# Sensor-TSL45315.net
KiCad netlist of a schematic drawn in EAGLE
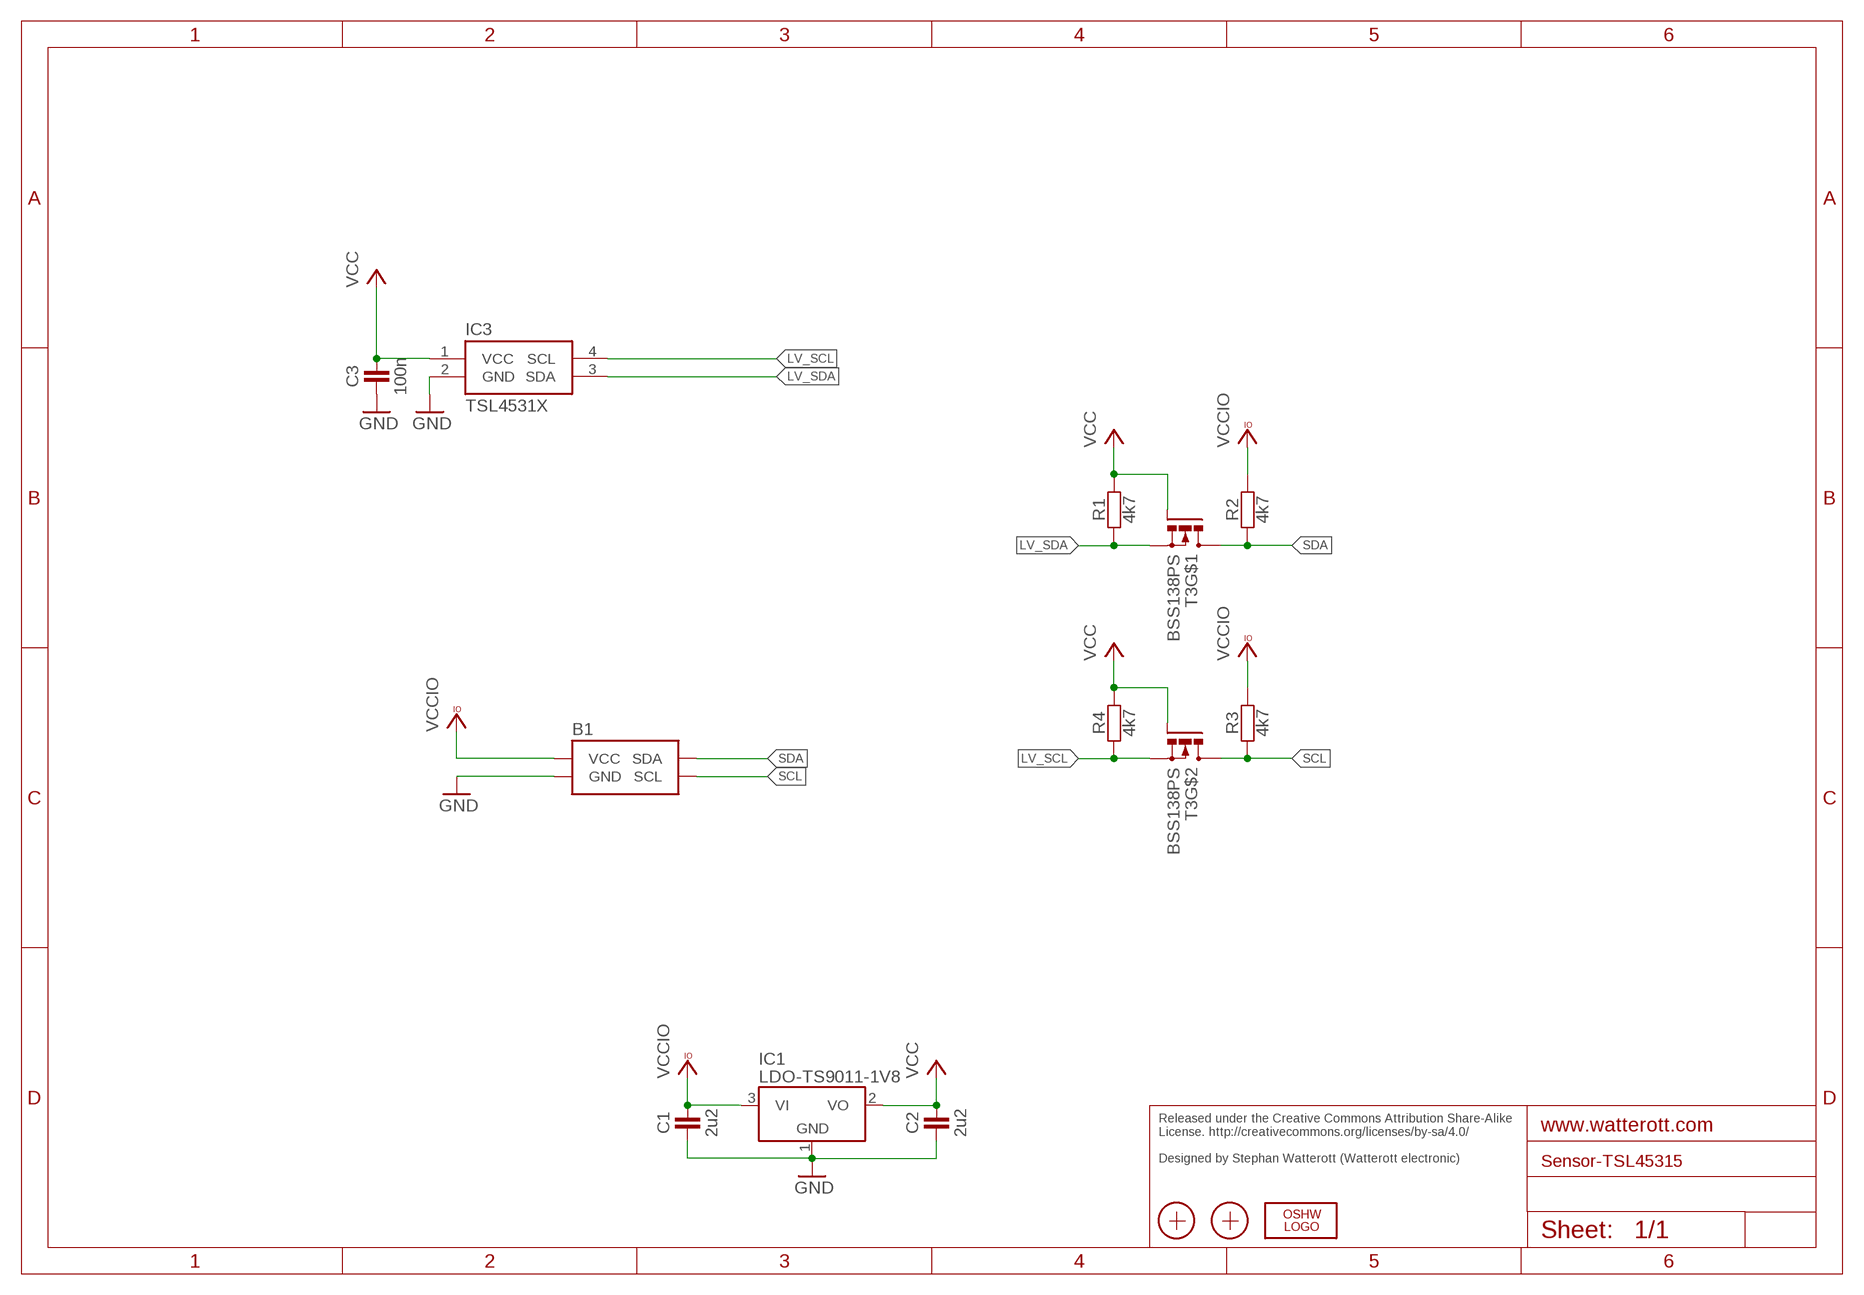
[diagram p0: schematic, sheet 1]

(export (version "E")
  (design (tool "Eeschema 10.0.6"))
  (components
    (comp (ref "B1")
      (value "SENSEBOX_I2C")
      (footprint "eagle-import:SENSEBOX_I2C")
      (libsource (lib "eagle-import") (part "SENSEBOX_I2C"))
    )
    (comp (ref "C1")
      (value "2u2")
      (footprint "eagle-import:R0402")
      (libsource (lib "eagle-import") (part "CAPACITOR-C0402"))
    )
    (comp (ref "C2")
      (value "2u2")
      (footprint "eagle-import:R0402")
      (libsource (lib "eagle-import") (part "CAPACITOR-C0402"))
    )
    (comp (ref "C3")
      (value "100n")
      (footprint "eagle-import:R0402")
      (libsource (lib "eagle-import") (part "CAPACITOR-C0402"))
    )
    (comp (ref "IC1")
      (value "LDO-TS9011-1V8")
      (footprint "eagle-import:SOT23")
      (libsource (lib "eagle-import") (part "LDO-TS9011-3V3"))
    )
    (comp (ref "IC3")
      (value "TSL4531X")
      (footprint "eagle-import:AMS_CL")
      (libsource (lib "eagle-import") (part "TSL4531X"))
    )
    (comp (ref "LOGO2")
      (value "OSHW_LOGOX0070")
      (footprint "eagle-import:OSHW_6X70")
      (libsource (lib "eagle-import") (part "OSHW_LOGOX0070"))
    )
    (comp (ref "R1")
      (value "4k7")
      (footprint "eagle-import:R0402")
      (libsource (lib "eagle-import") (part "RESISTOR-R0402"))
    )
    (comp (ref "R2")
      (value "4k7")
      (footprint "eagle-import:R0402")
      (libsource (lib "eagle-import") (part "RESISTOR-R0402"))
    )
    (comp (ref "R3")
      (value "4k7")
      (footprint "eagle-import:R0402")
      (libsource (lib "eagle-import") (part "RESISTOR-R0402"))
    )
    (comp (ref "R4")
      (value "4k7")
      (footprint "eagle-import:R0402")
      (libsource (lib "eagle-import") (part "RESISTOR-R0402"))
    )
    (comp (ref "T3")
      (value "BSS138PS")
      (footprint "eagle-import:SOT363")
      (libsource (lib "eagle-import") (part "BSS138PS"))
    )
    (comp (ref "X1")
      (value "PASSER-07")
      (footprint "eagle-import:PASSER_07MM")
      (libsource (lib "eagle-import") (part "PASSER-07"))
    )
    (comp (ref "X2")
      (value "PASSER-07")
      (footprint "eagle-import:PASSER_07MM")
      (libsource (lib "eagle-import") (part "PASSER-07"))
    )
  )
  (nets
    (net (code "1") (name "GND") (class "Default")
      (node (ref "B1") (pin "GND") (pinfunction "GND_GND") (pintype "power_in"))
      (node (ref "C1") (pin "1") (pinfunction "1_1") (pintype "passive"))
      (node (ref "C2") (pin "1") (pinfunction "1_1") (pintype "passive"))
      (node (ref "C3") (pin "1") (pinfunction "1_1") (pintype "passive"))
      (node (ref "IC1") (pin "1") (pinfunction "GND_1") (pintype "passive"))
      (node (ref "IC3") (pin "2") (pinfunction "GND_2") (pintype "power_in"))
    )
    (net (code "2") (name "LV_SCL") (class "Default")
      (node (ref "IC3") (pin "4") (pinfunction "SCL_4") (pintype "input"))
      (node (ref "R4") (pin "1") (pinfunction "1_1") (pintype "passive"))
      (node (ref "T3") (pin "4") (pinfunction "S_4") (pintype "passive"))
    )
    (net (code "3") (name "LV_SDA") (class "Default")
      (node (ref "IC3") (pin "3") (pinfunction "SDA_3") (pintype "output"))
      (node (ref "R1") (pin "1") (pinfunction "1_1") (pintype "passive"))
      (node (ref "T3") (pin "1") (pinfunction "S_1") (pintype "passive"))
    )
    (net (code "4") (name "SCL") (class "Default")
      (node (ref "B1") (pin "SCL") (pinfunction "SCL_SCL") (pintype "bidirectional"))
      (node (ref "R3") (pin "1") (pinfunction "1_1") (pintype "passive"))
      (node (ref "T3") (pin "3") (pinfunction "D_3") (pintype "passive"))
    )
    (net (code "5") (name "SDA") (class "Default")
      (node (ref "B1") (pin "SDA") (pinfunction "SDA_SDA") (pintype "bidirectional"))
      (node (ref "R2") (pin "1") (pinfunction "1_1") (pintype "passive"))
      (node (ref "T3") (pin "6") (pinfunction "D_6") (pintype "passive"))
    )
    (net (code "6") (name "VCC") (class "Default")
      (node (ref "C2") (pin "2") (pinfunction "2_2") (pintype "passive"))
      (node (ref "C3") (pin "2") (pinfunction "2_2") (pintype "passive"))
      (node (ref "IC1") (pin "2") (pinfunction "VO_2") (pintype "passive"))
      (node (ref "IC3") (pin "1") (pinfunction "VCC_1") (pintype "power_in"))
      (node (ref "R1") (pin "2") (pinfunction "2_2") (pintype "passive"))
      (node (ref "R4") (pin "2") (pinfunction "2_2") (pintype "passive"))
      (node (ref "T3") (pin "2") (pinfunction "G_2") (pintype "passive"))
      (node (ref "T3") (pin "5") (pinfunction "G_5") (pintype "passive"))
    )
    (net (code "7") (name "VCCIO") (class "Default")
      (node (ref "B1") (pin "VCC") (pinfunction "VCC_VCC") (pintype "power_in"))
      (node (ref "C1") (pin "2") (pinfunction "2_2") (pintype "passive"))
      (node (ref "IC1") (pin "3") (pinfunction "VI_3") (pintype "input"))
      (node (ref "R2") (pin "2") (pinfunction "2_2") (pintype "passive"))
      (node (ref "R3") (pin "2") (pinfunction "2_2") (pintype "passive"))
    )
  )
)
